# SHT_5_I_Controller_07349-R5_L10.net
KiCad netlist of a schematic drawn in Altium Designer
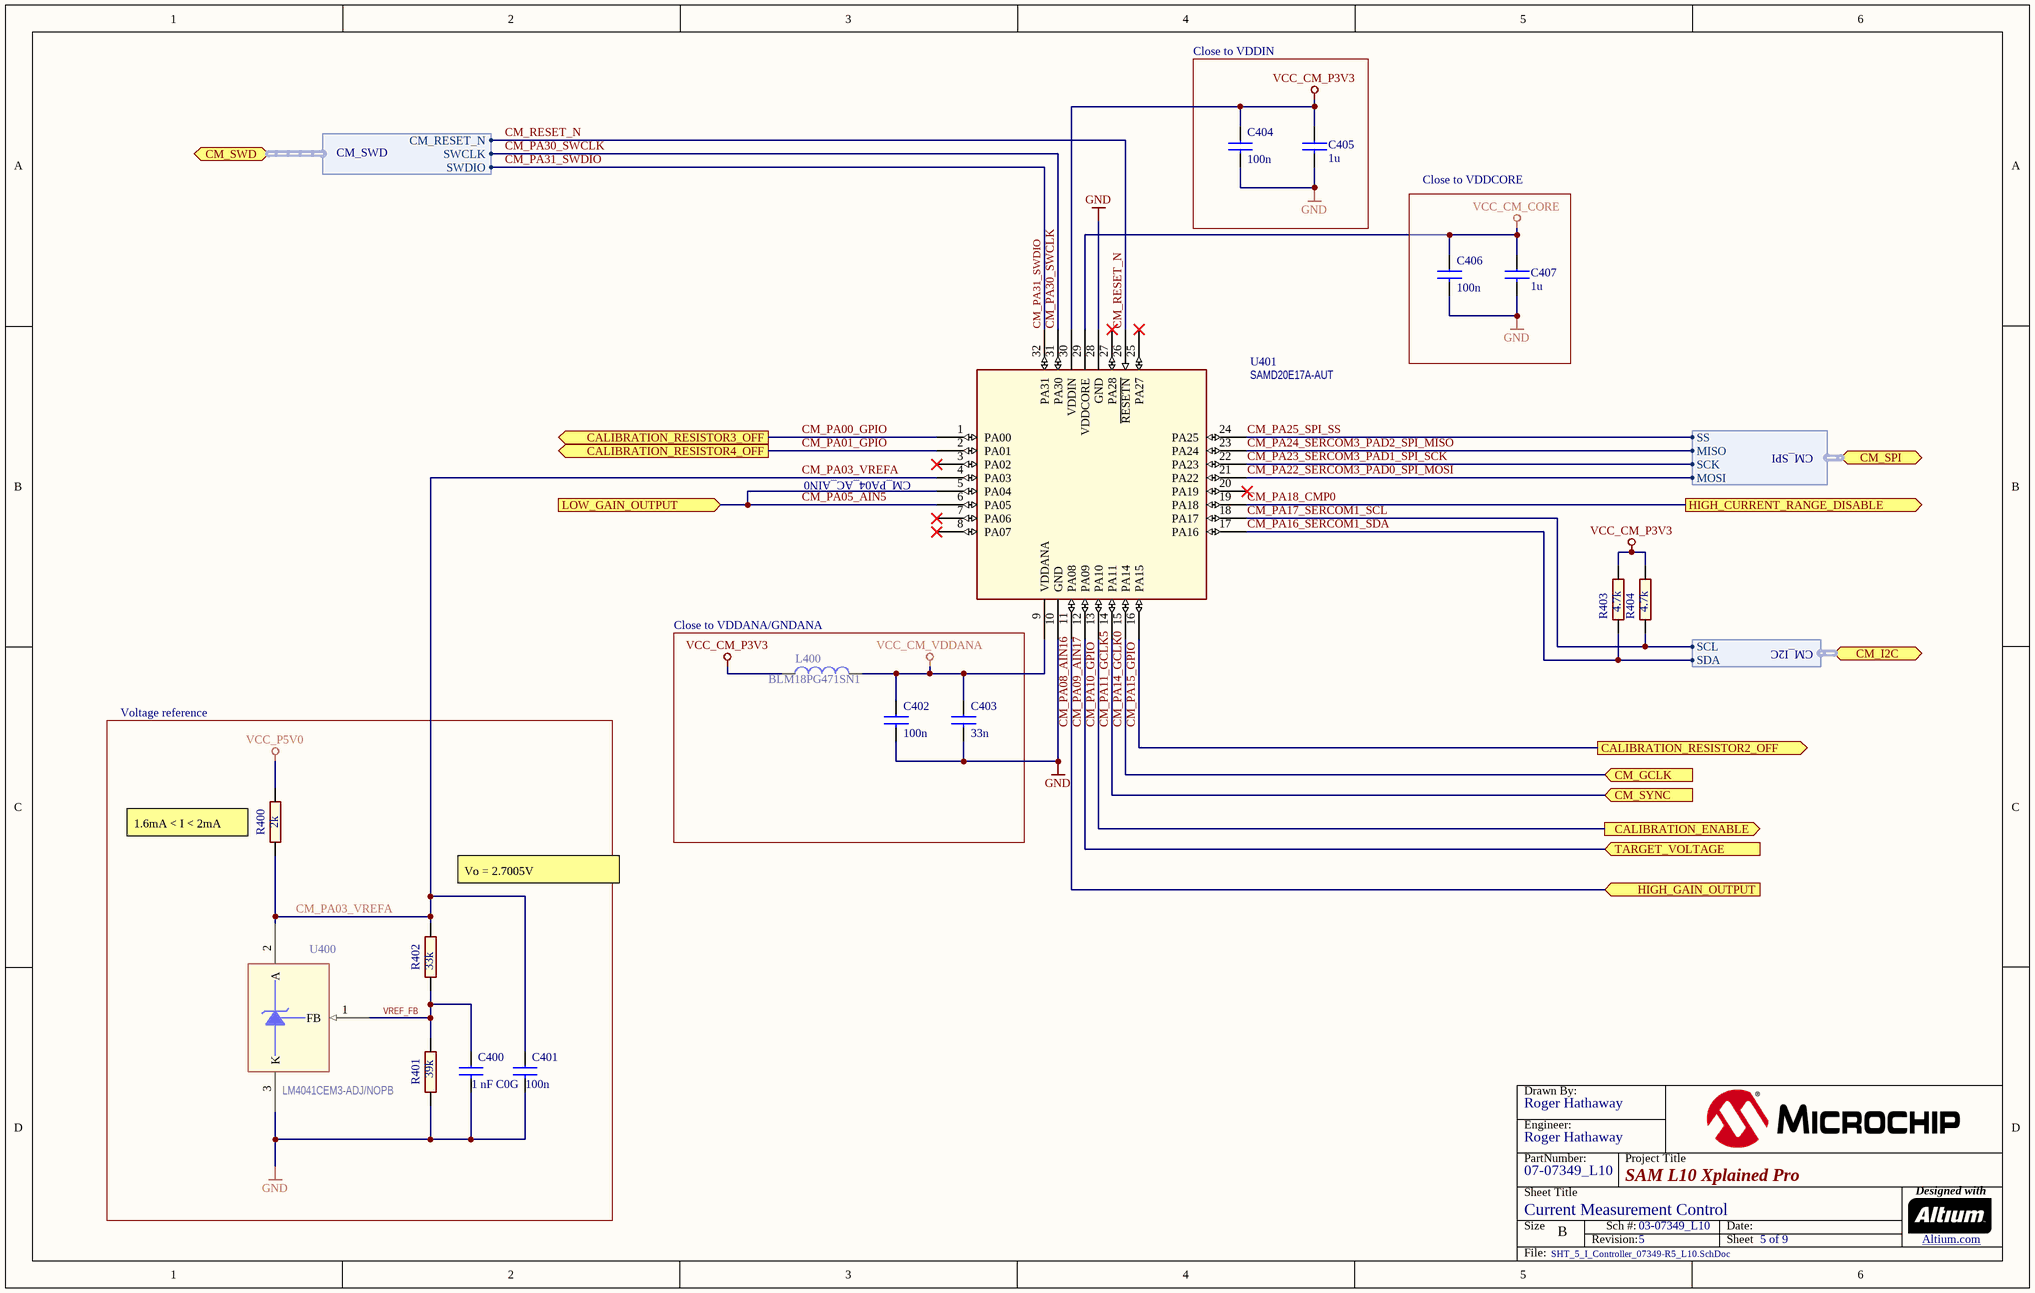
[diagram p0: SHT_5_I_Controller_07349-R5_L10.SchDoc]

(export (version "E")
  (design (tool "Eeschema 10.0.6"))
  (components
    (comp (ref "C400")
      (value "1 nF C0G")
      (footprint "AltiumDbLib:AP1-00053")
      (description "Ceramic capacitor, SMD 0402, C0G, 50V, +/-5%")
      (fields
        (field (name "TOLERANCE") "5%")
        (field (name "MANUFACTURER") "Murata")
        (field (name "VERIFIED BY") "Lars Helge Mo")
      )
      (libsource (lib "AltiumDbLib") (part "CAP-NONPOL"))
    )
    (comp (ref "C401")
      (value "100n")
      (footprint "AltiumDbLib:AP1-00053")
      (description "Ceramic capacitor, SMD 0402, X7R, 16V, +/-10%")
      (fields
        (field (name "TOLERANCE") "16V, +/-10%")
        (field (name "MANUFACTURER") "Kemet")
        (field (name "VERIFIED BY") "Lars Helge Mo")
      )
      (libsource (lib "AltiumDbLib") (part "CAP-NONPOL"))
    )
    (comp (ref "C402")
      (value "100n")
      (footprint "AltiumDbLib:AP1-00053")
      (description "Ceramic capacitor, SMD 0402, X7R, 16V, +/-10%")
      (fields
        (field (name "TOLERANCE") "16V, +/-10%")
        (field (name "MANUFACTURER") "Kemet")
        (field (name "VERIFIED BY") "Lars Helge Mo")
      )
      (libsource (lib "AltiumDbLib") (part "CAP-NONPOL"))
    )
    (comp (ref "C403")
      (value "33n")
      (footprint "AltiumDbLib:AP1-00053")
      (description "Ceramic capacitor, SMD 0402, X7R, 25V, ±10%")
      (fields
        (field (name "TOLERANCE") "±10%(K)")
        (field (name "MANUFACTURER") "Murata")
        (field (name "VERIFIED BY") "Lars Helge Mo")
      )
      (libsource (lib "AltiumDbLib") (part "CAP-NONPOL"))
    )
    (comp (ref "C404")
      (value "100n")
      (footprint "AltiumDbLib:AP1-00053")
      (description "Ceramic capacitor, SMD 0402, X7R, 16V, +/-10%")
      (fields
        (field (name "TOLERANCE") "16V, +/-10%")
        (field (name "MANUFACTURER") "Kemet")
        (field (name "VERIFIED BY") "Lars Helge Mo")
      )
      (libsource (lib "AltiumDbLib") (part "CAP-NONPOL"))
    )
    (comp (ref "C405")
      (value "1u")
      (footprint "AP1-00001")
      (description "Ceramic capacitor, SMD 0402, X5R, 6.3V, +/-10% (de26942)")
      (fields
        (field (name "TOLERANCE") "+/-10%")
        (field (name "MANUFACTURER") "Kemet")
        (field (name "VERIFIED BY") "Lars Helge Mo")
      )
      (libsource (lib "AltiumDbLib") (part "CAP-NONPOL"))
    )
    (comp (ref "C406")
      (value "100n")
      (footprint "AltiumDbLib:AP1-00053")
      (description "Ceramic capacitor, SMD 0402, X7R, 16V, +/-10%")
      (fields
        (field (name "TOLERANCE") "16V, +/-10%")
        (field (name "MANUFACTURER") "Kemet")
        (field (name "VERIFIED BY") "Lars Helge Mo")
      )
      (libsource (lib "AltiumDbLib") (part "CAP-NONPOL"))
    )
    (comp (ref "C407")
      (value "1u")
      (footprint "AP1-00001")
      (description "Ceramic capacitor, SMD 0402, X5R, 6.3V, +/-10% (de26942)")
      (fields
        (field (name "TOLERANCE") "+/-10%")
        (field (name "MANUFACTURER") "Kemet")
        (field (name "VERIFIED BY") "Lars Helge Mo")
      )
      (libsource (lib "AltiumDbLib") (part "CAP-NONPOL"))
    )
    (comp (ref "L400")
      (value "BLM18PG471SN1")
      (footprint "AltiumDbLib:AP3-00005")
      (description "SMD RF inductor 0603. Z=470Ohm (@100MHz), Max R(dc)=0.65Ohm, Max current=1A")
      (fields (field (name "MANUFACTURER") "Murata") (field (name "VERIFIED BY") "Lars Helge Mo"))
      (libsource (lib "AltiumDbLib") (part "INDUCTOR"))
    )
    (comp (ref "R400")
      (value "2k")
      (footprint "AltiumDbLib:AP2-00011")
      (description "Thick film resistor, SMD 0402, 1/16W, 1%")
      (fields
        (field (name "TOLERANCE") "1 %")
        (field (name "MPN") "RC0402FR-072KL")
        (field (name "VERIFIED BY") "Lars Helge Mo")
      )
      (libsource (lib "AltiumDbLib") (part "R2"))
    )
    (comp (ref "R401")
      (value "39k")
      (footprint "AltiumDbLib:AP2-00011")
      (description "Thick film resistor, SMD 0402, 1/16W, 1%")
      (fields
        (field (name "TOLERANCE") "1 %")
        (field (name "MANUFACTURER") "ASJ")
        (field (name "VERIFIED BY") "Lars Helge Mo")
      )
      (libsource (lib "AltiumDbLib") (part "R2"))
    )
    (comp (ref "R402")
      (value "33k")
      (footprint "AltiumDbLib:AP2-00011")
      (description "Thick film resistor, SMD 0402, 1/16W, 1%")
      (fields
        (field (name "TOLERANCE") "1 %")
        (field (name "MANUFACTURER") "ASJ")
        (field (name "VERIFIED BY") "Lars Helge Mo")
      )
      (libsource (lib "AltiumDbLib") (part "R2"))
    )
    (comp (ref "R403")
      (value "4.7k")
      (footprint "AltiumDbLib:AP2-00011")
      (description "Thick film resistor, SMD 0402, 1/16W, 1%")
      (fields
        (field (name "TOLERANCE") "1 %")
        (field (name "MANUFACTURER") "PHYCOMP")
        (field (name "VERIFIED BY") "Lars Helge Mo")
      )
      (libsource (lib "") (part "R2_1"))
    )
    (comp (ref "R404")
      (value "4.7k")
      (footprint "AltiumDbLib:AP2-00011")
      (description "Thick film resistor, SMD 0402, 1/16W, 1%")
      (fields
        (field (name "TOLERANCE") "1 %")
        (field (name "MANUFACTURER") "PHYCOMP")
        (field (name "VERIFIED BY") "Lars Helge Mo")
      )
      (libsource (lib "") (part "R2_1"))
    )
    (comp (ref "U400")
      (value "LM4041CEM3-ADJ/NOPB")
      (footprint "AP5-00002")
      (description "Adjustable shunt voltage regulator, 1.24 to 10V out")
      (fields
        (field (name "MANUFACTURER") "Texas Instruments")
        (field (name "Comment") "Updated with No-Pb part number and Texas Instruments mfc.")
      )
      (libsource (lib "AltiumDbLib") (part "LM4041-ADJ"))
    )
    (comp (ref "U401")
      (value "SAMD20E17A-AUT")
      (footprint "AP6-00061")
      (description "Atmel 32bit RISC MCU 32 pin")
      (fields
        (field (name "MANUFACTURER") "ATMEL")
        (field (name "MPN") "ATSAMD20E17A-AUT")
        (field (name "VERIFIED BY") "*")
      )
      (libsource (lib "AltiumDbLib") (part "SAMD20E"))
    )
  )
  (nets
    (net (code "4") (name "/CM_PA00_GPIO") (class "Default")
      (node (ref "U401") (pin "1") (pinfunction "PA00_1") (pintype "bidirectional"))
    )
    (net (code "5") (name "/CM_PA01_GPIO") (class "Default")
      (node (ref "U401") (pin "2") (pinfunction "PA01_2") (pintype "bidirectional"))
    )
    (net (code "6") (name "/CM_PA03_VREFA") (class "Default")
      (node (ref "C401") (pin "1") (pinfunction "1_1") (pintype "passive"))
      (node (ref "R400") (pin "1") (pinfunction "1_1") (pintype "passive"))
      (node (ref "R402") (pin "2") (pinfunction "2_2") (pintype "passive"))
      (node (ref "U400") (pin "2") (pinfunction "A_2") (pintype "power_in"))
      (node (ref "U401") (pin "4") (pinfunction "PA03_4") (pintype "bidirectional"))
    )
    (net (code "7") (name "/CM_PA05_AIN5") (class "Default")
      (node (ref "U401") (pin "5") (pinfunction "PA04_5") (pintype "bidirectional"))
      (node (ref "U401") (pin "6") (pinfunction "PA05_6") (pintype "bidirectional"))
    )
    (net (code "8") (name "/CM_PA08_AIN16") (class "Default")
      (node (ref "U401") (pin "11") (pinfunction "PA08_11") (pintype "bidirectional"))
    )
    (net (code "9") (name "/CM_PA09_AIN17") (class "Default")
      (node (ref "U401") (pin "12") (pinfunction "PA09_12") (pintype "bidirectional"))
    )
    (net (code "10") (name "/CM_PA10_GPIO") (class "Default")
      (node (ref "U401") (pin "13") (pinfunction "PA10_13") (pintype "bidirectional"))
    )
    (net (code "11") (name "/CM_PA11_GCLK5") (class "Default")
      (node (ref "U401") (pin "14") (pinfunction "PA11_14") (pintype "bidirectional"))
    )
    (net (code "12") (name "/CM_PA14_GCLK0") (class "Default")
      (node (ref "U401") (pin "15") (pinfunction "PA14_15") (pintype "bidirectional"))
    )
    (net (code "13") (name "/CM_PA15_GPIO") (class "Default")
      (node (ref "U401") (pin "16") (pinfunction "PA15_16") (pintype "bidirectional"))
    )
    (net (code "14") (name "/CM_PA16_SERCOM1_SDA") (class "Default")
      (node (ref "R403") (pin "1") (pinfunction "1_1") (pintype "passive"))
      (node (ref "U401") (pin "17") (pinfunction "PA16_17") (pintype "bidirectional"))
    )
    (net (code "15") (name "/CM_PA17_SERCOM1_SCL") (class "Default")
      (node (ref "R404") (pin "1") (pinfunction "1_1") (pintype "passive"))
      (node (ref "U401") (pin "18") (pinfunction "PA17_18") (pintype "bidirectional"))
    )
    (net (code "16") (name "/CM_PA18_CMP0") (class "Default")
      (node (ref "U401") (pin "19") (pinfunction "PA18_19") (pintype "bidirectional"))
    )
    (net (code "17") (name "/CM_PA22_SERCOM3_PAD0_SPI_MOSI") (class "Default")
      (node (ref "U401") (pin "21") (pinfunction "PA22_21") (pintype "bidirectional"))
    )
    (net (code "18") (name "/CM_PA23_SERCOM3_PAD1_SPI_SCK") (class "Default")
      (node (ref "U401") (pin "22") (pinfunction "PA23_22") (pintype "bidirectional"))
    )
    (net (code "19") (name "/CM_PA24_SERCOM3_PAD2_SPI_MISO") (class "Default")
      (node (ref "U401") (pin "23") (pinfunction "PA24_23") (pintype "bidirectional"))
    )
    (net (code "20") (name "/CM_PA25_SPI_SS") (class "Default")
      (node (ref "U401") (pin "24") (pinfunction "PA25_24") (pintype "bidirectional"))
    )
    (net (code "21") (name "/CM_PA30_SWCLK") (class "Default")
      (node (ref "U401") (pin "31") (pinfunction "PA30_31") (pintype "bidirectional"))
    )
    (net (code "22") (name "/CM_PA31_SWDIO") (class "Default")
      (node (ref "U401") (pin "32") (pinfunction "PA31_32") (pintype "bidirectional"))
    )
    (net (code "23") (name "/CM_RESET_N") (class "Default")
      (node (ref "U401") (pin "26") (pinfunction "~{RESETN}_26") (pintype "input"))
    )
    (net (code "24") (name "/VREF_FB") (class "Default")
      (node (ref "C400") (pin "1") (pinfunction "1_1") (pintype "passive"))
      (node (ref "R401") (pin "2") (pinfunction "2_2") (pintype "passive"))
      (node (ref "R402") (pin "1") (pinfunction "1_1") (pintype "passive"))
      (node (ref "U400") (pin "1") (pinfunction "FB_1") (pintype "input"))
    )
    (net (code "28") (name "GND") (class "Default")
      (node (ref "C400") (pin "2") (pinfunction "2_2") (pintype "passive"))
      (node (ref "C401") (pin "2") (pinfunction "2_2") (pintype "passive"))
      (node (ref "C402") (pin "2") (pinfunction "2_2") (pintype "passive"))
      (node (ref "C403") (pin "2") (pinfunction "2_2") (pintype "passive"))
      (node (ref "C404") (pin "2") (pinfunction "2_2") (pintype "passive"))
      (node (ref "C405") (pin "2") (pinfunction "2_2") (pintype "passive"))
      (node (ref "C406") (pin "2") (pinfunction "2_2") (pintype "passive"))
      (node (ref "C407") (pin "2") (pinfunction "2_2") (pintype "passive"))
      (node (ref "R401") (pin "1") (pinfunction "1_1") (pintype "passive"))
      (node (ref "U400") (pin "3") (pinfunction "K_3") (pintype "power_in"))
      (node (ref "U401") (pin "10") (pinfunction "GND_10") (pintype "power_in"))
      (node (ref "U401") (pin "28") (pinfunction "GND_28") (pintype "power_in"))
    )
    (net (code "29") (name "VCC_CM_CORE") (class "Default")
      (node (ref "C406") (pin "1") (pinfunction "1_1") (pintype "passive"))
      (node (ref "C407") (pin "1") (pinfunction "1_1") (pintype "passive"))
      (node (ref "U401") (pin "29") (pinfunction "VDDCORE_29") (pintype "power_in"))
    )
    (net (code "30") (name "VCC_CM_P3V3") (class "Default")
      (node (ref "C404") (pin "1") (pinfunction "1_1") (pintype "passive"))
      (node (ref "C405") (pin "1") (pinfunction "1_1") (pintype "passive"))
      (node (ref "L400") (pin "1") (pinfunction "1_1") (pintype "passive"))
      (node (ref "R403") (pin "2") (pinfunction "2_2") (pintype "passive"))
      (node (ref "R404") (pin "2") (pinfunction "2_2") (pintype "passive"))
      (node (ref "U401") (pin "30") (pinfunction "VDDIN_30") (pintype "power_in"))
    )
    (net (code "31") (name "VCC_CM_VDDANA") (class "Default")
      (node (ref "C402") (pin "1") (pinfunction "1_1") (pintype "passive"))
      (node (ref "C403") (pin "1") (pinfunction "1_1") (pintype "passive"))
      (node (ref "L400") (pin "2") (pinfunction "2_2") (pintype "passive"))
      (node (ref "U401") (pin "9") (pinfunction "VDDANA_9") (pintype "power_in"))
    )
    (net (code "32") (name "VCC_P5V0") (class "Default")
      (node (ref "R400") (pin "2") (pinfunction "2_2") (pintype "passive"))
    )
    (net (code "33") (name "unconnected-(U401-PA02-Pad3)") (class "Default")
      (node (ref "U401") (pin "3") (pinfunction "PA02_3") (pintype "bidirectional+no_connect"))
    )
    (net (code "34") (name "unconnected-(U401-PA06-Pad7)") (class "Default")
      (node (ref "U401") (pin "7") (pinfunction "PA06_7") (pintype "bidirectional+no_connect"))
    )
    (net (code "35") (name "unconnected-(U401-PA07-Pad8)") (class "Default")
      (node (ref "U401") (pin "8") (pinfunction "PA07_8") (pintype "bidirectional+no_connect"))
    )
    (net (code "36") (name "unconnected-(U401-PA19-Pad20)") (class "Default")
      (node (ref "U401") (pin "20") (pinfunction "PA19_20") (pintype "bidirectional+no_connect"))
    )
    (net (code "37") (name "unconnected-(U401-PA27-Pad25)") (class "Default")
      (node (ref "U401") (pin "25") (pinfunction "PA27_25") (pintype "bidirectional+no_connect"))
    )
    (net (code "38") (name "unconnected-(U401-PA28-Pad27)") (class "Default")
      (node (ref "U401") (pin "27") (pinfunction "PA28_27") (pintype "bidirectional+no_connect"))
    )
  )
)
